# STeaMi-FP9-Bouton_de_controle.net
KiCad netlist of a schematic drawn in Altium Designer
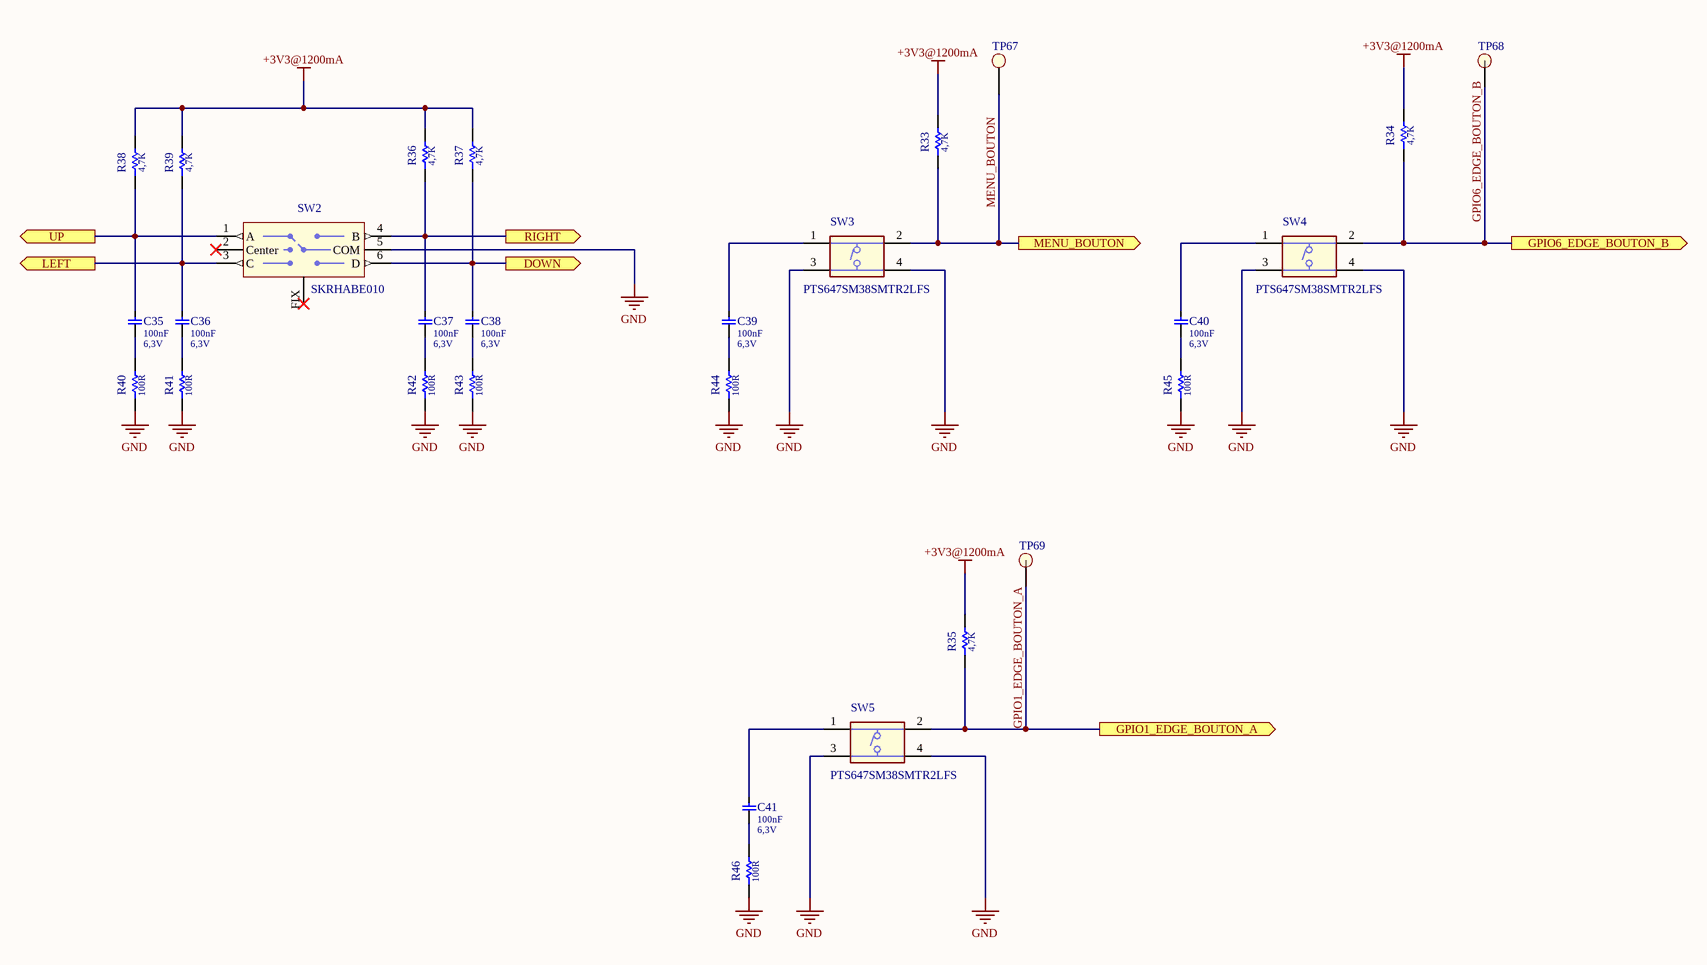
[diagram p0: STeaMi-FP9-Bouton_de_controle.SchDoc]

(export (version "E")
  (design (tool "Eeschema 10.0.6"))
  (components
    (comp (ref "C35")
      (value "~")
      (footprint "0402-CAP")
      (description "CAP CER 100nF 6,3V X5R 0402")
      (fields
        (field (name "MANUFACTURER") "Kyocera AVX")
        (field (name "MANUFACTURER PART NUMBER") "0402YD104KAT2A")
        (field (name "CAPACITANCE") "100nF")
        (field (name "VOLTAGE") "6,3V")
        (field (name "CREATED BY") "EAG")
        (field (name "CHECKED BY") "*")
      )
      (libsource (lib "ComponentDB") (part "CAP_SYMBOL"))
    )
    (comp (ref "C36")
      (value "~")
      (footprint "0402-CAP")
      (description "CAP CER 100nF 6,3V X5R 0402")
      (fields
        (field (name "MANUFACTURER") "Kyocera AVX")
        (field (name "MANUFACTURER PART NUMBER") "0402YD104KAT2A")
        (field (name "CAPACITANCE") "100nF")
        (field (name "VOLTAGE") "6,3V")
        (field (name "CREATED BY") "EAG")
        (field (name "CHECKED BY") "*")
      )
      (libsource (lib "ComponentDB") (part "CAP_SYMBOL"))
    )
    (comp (ref "C37")
      (value "~")
      (footprint "0402-CAP")
      (description "CAP CER 100nF 6,3V X5R 0402")
      (fields
        (field (name "MANUFACTURER") "Kyocera AVX")
        (field (name "MANUFACTURER PART NUMBER") "0402YD104KAT2A")
        (field (name "CAPACITANCE") "100nF")
        (field (name "VOLTAGE") "6,3V")
        (field (name "CREATED BY") "EAG")
        (field (name "CHECKED BY") "*")
      )
      (libsource (lib "ComponentDB") (part "CAP_SYMBOL"))
    )
    (comp (ref "C38")
      (value "~")
      (footprint "0402-CAP")
      (description "CAP CER 100nF 6,3V X5R 0402")
      (fields
        (field (name "MANUFACTURER") "Kyocera AVX")
        (field (name "MANUFACTURER PART NUMBER") "0402YD104KAT2A")
        (field (name "CAPACITANCE") "100nF")
        (field (name "VOLTAGE") "6,3V")
        (field (name "CREATED BY") "EAG")
        (field (name "CHECKED BY") "*")
      )
      (libsource (lib "ComponentDB") (part "CAP_SYMBOL"))
    )
    (comp (ref "C39")
      (value "~")
      (footprint "0402-CAP")
      (description "CAP CER 100nF 6,3V X5R 0402")
      (fields
        (field (name "MANUFACTURER") "Kyocera AVX")
        (field (name "MANUFACTURER PART NUMBER") "0402YD104KAT2A")
        (field (name "CAPACITANCE") "100nF")
        (field (name "VOLTAGE") "6,3V")
        (field (name "CREATED BY") "EAG")
        (field (name "CHECKED BY") "*")
      )
      (libsource (lib "ComponentDB") (part "CAP_SYMBOL"))
    )
    (comp (ref "C40")
      (value "~")
      (footprint "0402-CAP")
      (description "CAP CER 100nF 6,3V X5R 0402")
      (fields
        (field (name "MANUFACTURER") "Kyocera AVX")
        (field (name "MANUFACTURER PART NUMBER") "0402YD104KAT2A")
        (field (name "CAPACITANCE") "100nF")
        (field (name "VOLTAGE") "6,3V")
        (field (name "CREATED BY") "EAG")
        (field (name "CHECKED BY") "*")
      )
      (libsource (lib "ComponentDB") (part "CAP_SYMBOL"))
    )
    (comp (ref "C41")
      (value "~")
      (footprint "0402-CAP")
      (description "CAP CER 100nF 6,3V X5R 0402")
      (fields
        (field (name "MANUFACTURER") "Kyocera AVX")
        (field (name "MANUFACTURER PART NUMBER") "0402YD104KAT2A")
        (field (name "CAPACITANCE") "100nF")
        (field (name "VOLTAGE") "6,3V")
        (field (name "CREATED BY") "EAG")
        (field (name "CHECKED BY") "*")
      )
      (libsource (lib "ComponentDB") (part "CAP_SYMBOL"))
    )
    (comp (ref "R33")
      (value "~")
      (footprint "RESC1005X40N_0402")
      (description "RES CMS 4,7K5%-0,0625W-0402 ±100ppm/°C")
      (fields
        (field (name "MANUFACTURER") "Yageo")
        (field (name "MANUFACTURER PART NUMBER") "AC0402JR-074K7L")
        (field (name "RESISTANCE") "4,7K")
        (field (name "CREATED BY") "EAG")
      )
      (libsource (lib "ComponentDB") (part "RES_SYMBOL"))
    )
    (comp (ref "R34")
      (value "~")
      (footprint "RESC1005X40N_0402")
      (description "RES CMS 4,7K5%-0,0625W-0402 ±100ppm/°C")
      (fields
        (field (name "MANUFACTURER") "Yageo")
        (field (name "MANUFACTURER PART NUMBER") "AC0402JR-074K7L")
        (field (name "RESISTANCE") "4,7K")
        (field (name "CREATED BY") "EAG")
      )
      (libsource (lib "ComponentDB") (part "RES_SYMBOL"))
    )
    (comp (ref "R35")
      (value "~")
      (footprint "RESC1005X40N_0402")
      (description "RES CMS 4,7K5%-0,0625W-0402 ±100ppm/°C")
      (fields
        (field (name "MANUFACTURER") "Yageo")
        (field (name "MANUFACTURER PART NUMBER") "AC0402JR-074K7L")
        (field (name "RESISTANCE") "4,7K")
        (field (name "CREATED BY") "EAG")
      )
      (libsource (lib "ComponentDB") (part "RES_SYMBOL"))
    )
    (comp (ref "R36")
      (value "~")
      (footprint "RESC1005X40N_0402")
      (description "RES CMS 4,7K5%-0,0625W-0402 ±100ppm/°C")
      (fields
        (field (name "MANUFACTURER") "Yageo")
        (field (name "MANUFACTURER PART NUMBER") "AC0402JR-074K7L")
        (field (name "RESISTANCE") "4,7K")
        (field (name "CREATED BY") "EAG")
      )
      (libsource (lib "ComponentDB") (part "RES_SYMBOL"))
    )
    (comp (ref "R37")
      (value "~")
      (footprint "RESC1005X40N_0402")
      (description "RES CMS 4,7K5%-0,0625W-0402 ±100ppm/°C")
      (fields
        (field (name "MANUFACTURER") "Yageo")
        (field (name "MANUFACTURER PART NUMBER") "AC0402JR-074K7L")
        (field (name "RESISTANCE") "4,7K")
        (field (name "CREATED BY") "EAG")
      )
      (libsource (lib "ComponentDB") (part "RES_SYMBOL"))
    )
    (comp (ref "R38")
      (value "~")
      (footprint "RESC1005X40N_0402")
      (description "RES CMS 4,7K5%-0,0625W-0402 ±100ppm/°C")
      (fields
        (field (name "MANUFACTURER") "Yageo")
        (field (name "MANUFACTURER PART NUMBER") "AC0402JR-074K7L")
        (field (name "RESISTANCE") "4,7K")
        (field (name "CREATED BY") "EAG")
      )
      (libsource (lib "ComponentDB") (part "RES_SYMBOL"))
    )
    (comp (ref "R39")
      (value "~")
      (footprint "RESC1005X40N_0402")
      (description "RES CMS 4,7K5%-0,0625W-0402 ±100ppm/°C")
      (fields
        (field (name "MANUFACTURER") "Yageo")
        (field (name "MANUFACTURER PART NUMBER") "AC0402JR-074K7L")
        (field (name "RESISTANCE") "4,7K")
        (field (name "CREATED BY") "EAG")
      )
      (libsource (lib "ComponentDB") (part "RES_SYMBOL"))
    )
    (comp (ref "R40")
      (value "~")
      (footprint "RESC1005X40N_0402")
      (description "RES CMS 100R5%-0,0625W-0402 ±100ppm/°C")
      (fields
        (field (name "MANUFACTURER") "Yageo")
        (field (name "MANUFACTURER PART NUMBER") "RC0402JR-07100RL")
        (field (name "RESISTANCE") "100R")
        (field (name "CREATED BY") "EAG")
      )
      (libsource (lib "ComponentDB") (part "RES_SYMBOL"))
    )
    (comp (ref "R41")
      (value "~")
      (footprint "RESC1005X40N_0402")
      (description "RES CMS 100R5%-0,0625W-0402 ±100ppm/°C")
      (fields
        (field (name "MANUFACTURER") "Yageo")
        (field (name "MANUFACTURER PART NUMBER") "RC0402JR-07100RL")
        (field (name "RESISTANCE") "100R")
        (field (name "CREATED BY") "EAG")
      )
      (libsource (lib "ComponentDB") (part "RES_SYMBOL"))
    )
    (comp (ref "R42")
      (value "~")
      (footprint "RESC1005X40N_0402")
      (description "RES CMS 100R5%-0,0625W-0402 ±100ppm/°C")
      (fields
        (field (name "MANUFACTURER") "Yageo")
        (field (name "MANUFACTURER PART NUMBER") "RC0402JR-07100RL")
        (field (name "RESISTANCE") "100R")
        (field (name "CREATED BY") "EAG")
      )
      (libsource (lib "ComponentDB") (part "RES_SYMBOL"))
    )
    (comp (ref "R43")
      (value "~")
      (footprint "RESC1005X40N_0402")
      (description "RES CMS 100R5%-0,0625W-0402 ±100ppm/°C")
      (fields
        (field (name "MANUFACTURER") "Yageo")
        (field (name "MANUFACTURER PART NUMBER") "RC0402JR-07100RL")
        (field (name "RESISTANCE") "100R")
        (field (name "CREATED BY") "EAG")
      )
      (libsource (lib "ComponentDB") (part "RES_SYMBOL"))
    )
    (comp (ref "R44")
      (value "~")
      (footprint "RESC1005X40N_0402")
      (description "RES CMS 100R5%-0,0625W-0402 ±100ppm/°C")
      (fields
        (field (name "MANUFACTURER") "Yageo")
        (field (name "MANUFACTURER PART NUMBER") "RC0402JR-07100RL")
        (field (name "RESISTANCE") "100R")
        (field (name "CREATED BY") "EAG")
      )
      (libsource (lib "ComponentDB") (part "RES_SYMBOL"))
    )
    (comp (ref "R45")
      (value "~")
      (footprint "RESC1005X40N_0402")
      (description "RES CMS 100R5%-0,0625W-0402 ±100ppm/°C")
      (fields
        (field (name "MANUFACTURER") "Yageo")
        (field (name "MANUFACTURER PART NUMBER") "RC0402JR-07100RL")
        (field (name "RESISTANCE") "100R")
        (field (name "CREATED BY") "EAG")
      )
      (libsource (lib "ComponentDB") (part "RES_SYMBOL"))
    )
    (comp (ref "R46")
      (value "~")
      (footprint "RESC1005X40N_0402")
      (description "RES CMS 100R5%-0,0625W-0402 ±100ppm/°C")
      (fields
        (field (name "MANUFACTURER") "Yageo")
        (field (name "MANUFACTURER PART NUMBER") "RC0402JR-07100RL")
        (field (name "RESISTANCE") "100R")
        (field (name "CREATED BY") "EAG")
      )
      (libsource (lib "ComponentDB") (part "RES_SYMBOL"))
    )
    (comp (ref "SW2")
      (value "~")
      (footprint "SKRHABE010")
      (description "4-direction type with center-push function")
      (fields
        (field (name "MANUFACTURER") "ALPS")
        (field (name "MANUFACTURER PART NUMBER") "SKRHABE010")
        (field (name "PART NUMBER") "SKRHABE010")
        (field (name "CREATED BY") "EAG")
        (field (name "CHECKED BY") "*")
      )
      (libsource (lib "ComponentDB") (part "SKRHABE010"))
    )
    (comp (ref "SW3")
      (value "~")
      (footprint "PTS647SM38SMTR2LFS")
      (description "Interrupteurs de contact 50mA 12VDC, 1.8N 3.8mm H, G leads")
      (fields
        (field (name "MANUFACTURER") "C&K")
        (field (name "MANUFACTURER PART NUMBER") "PTS647SM38SMTR2LFS")
        (field (name "PART NUMBER") "PTS647SM38SMTR2LFS")
        (field (name "CREATED BY") "EAG")
        (field (name "CHECKED BY") "*")
      )
      (libsource (lib "ComponentDB") (part "PTS647SM38SMTR2LFS"))
    )
    (comp (ref "SW4")
      (value "~")
      (footprint "PTS647SM38SMTR2LFS")
      (description "Interrupteurs de contact 50mA 12VDC, 1.8N 3.8mm H, G leads")
      (fields
        (field (name "MANUFACTURER") "C&K")
        (field (name "MANUFACTURER PART NUMBER") "PTS647SM38SMTR2LFS")
        (field (name "PART NUMBER") "PTS647SM38SMTR2LFS")
        (field (name "CREATED BY") "EAG")
        (field (name "CHECKED BY") "*")
      )
      (libsource (lib "ComponentDB") (part "PTS647SM38SMTR2LFS"))
    )
    (comp (ref "SW5")
      (value "~")
      (footprint "PTS647SM38SMTR2LFS")
      (description "Interrupteurs de contact 50mA 12VDC, 1.8N 3.8mm H, G leads")
      (fields
        (field (name "MANUFACTURER") "C&K")
        (field (name "MANUFACTURER PART NUMBER") "PTS647SM38SMTR2LFS")
        (field (name "PART NUMBER") "PTS647SM38SMTR2LFS")
        (field (name "CREATED BY") "EAG")
        (field (name "CHECKED BY") "*")
      )
      (libsource (lib "ComponentDB") (part "PTS647SM38SMTR2LFS"))
    )
    (comp (ref "TP67")
      (value "PAD")
      (footprint "Testpoint 1mm")
      (description "TESTPOINTPAD")
      (fields (field (name "MANUFACTURER") "SmartEmbed"))
      (libsource (lib "") (part "TESTPOINT_1"))
    )
    (comp (ref "TP68")
      (value "PAD")
      (footprint "Testpoint 1mm")
      (description "TESTPOINTPAD")
      (fields (field (name "MANUFACTURER") "SmartEmbed"))
      (libsource (lib "ComponentDB") (part "TESTPOINT"))
    )
    (comp (ref "TP69")
      (value "PAD")
      (footprint "Testpoint 1mm")
      (description "TESTPOINTPAD")
      (fields (field (name "MANUFACTURER") "SmartEmbed"))
      (libsource (lib "ComponentDB") (part "TESTPOINT"))
    )
  )
  (nets
    (net (code "1") (name "+3V3@1200mA") (class "Default")
      (node (ref "R33") (pin "2") (pinfunction "2_2") (pintype "passive"))
      (node (ref "R34") (pin "2") (pinfunction "2_2") (pintype "passive"))
      (node (ref "R35") (pin "2") (pinfunction "2_2") (pintype "passive"))
      (node (ref "R36") (pin "2") (pinfunction "2_2") (pintype "passive"))
      (node (ref "R37") (pin "2") (pinfunction "2_2") (pintype "passive"))
      (node (ref "R38") (pin "2") (pinfunction "2_2") (pintype "passive"))
      (node (ref "R39") (pin "2") (pinfunction "2_2") (pintype "passive"))
    )
    (net (code "2") (name "/DOWN") (class "Default")
      (node (ref "C38") (pin "2") (pinfunction "2_2") (pintype "passive"))
      (node (ref "R37") (pin "1") (pinfunction "1_1") (pintype "passive"))
      (node (ref "SW2") (pin "6") (pinfunction "D_6") (pintype "output"))
    )
    (net (code "3") (name "/GPIO1_EDGE_BOUTON_A") (class "Default")
      (node (ref "R35") (pin "1") (pinfunction "1_1") (pintype "passive"))
      (node (ref "SW5") (pin "2") (pinfunction "2_2") (pintype "passive"))
      (node (ref "TP69") (pin "1") (pinfunction "1_1") (pintype "passive"))
    )
    (net (code "4") (name "/GPIO6_EDGE_BOUTON_B") (class "Default")
      (node (ref "R34") (pin "1") (pinfunction "1_1") (pintype "passive"))
      (node (ref "SW4") (pin "2") (pinfunction "2_2") (pintype "passive"))
      (node (ref "TP68") (pin "1") (pinfunction "1_1") (pintype "passive"))
    )
    (net (code "5") (name "/LEFT") (class "Default")
      (node (ref "C36") (pin "2") (pinfunction "2_2") (pintype "passive"))
      (node (ref "R39") (pin "1") (pinfunction "1_1") (pintype "passive"))
      (node (ref "SW2") (pin "3") (pinfunction "C_3") (pintype "output"))
    )
    (net (code "6") (name "/MENU_BOUTON") (class "Default")
      (node (ref "R33") (pin "1") (pinfunction "1_1") (pintype "passive"))
      (node (ref "SW3") (pin "2") (pinfunction "2_2") (pintype "passive"))
      (node (ref "TP67") (pin "1") (pinfunction "1_1") (pintype "passive"))
    )
    (net (code "7") (name "/RIGHT") (class "Default")
      (node (ref "C37") (pin "2") (pinfunction "2_2") (pintype "passive"))
      (node (ref "R36") (pin "1") (pinfunction "1_1") (pintype "passive"))
      (node (ref "SW2") (pin "4") (pinfunction "B_4") (pintype "output"))
    )
    (net (code "8") (name "/UP") (class "Default")
      (node (ref "C35") (pin "2") (pinfunction "2_2") (pintype "passive"))
      (node (ref "R38") (pin "1") (pinfunction "1_1") (pintype "passive"))
      (node (ref "SW2") (pin "1") (pinfunction "A_1") (pintype "output"))
    )
    (net (code "9") (name "GND") (class "Default")
      (node (ref "R40") (pin "1") (pinfunction "1_1") (pintype "passive"))
      (node (ref "R41") (pin "1") (pinfunction "1_1") (pintype "passive"))
      (node (ref "R42") (pin "1") (pinfunction "1_1") (pintype "passive"))
      (node (ref "R43") (pin "1") (pinfunction "1_1") (pintype "passive"))
      (node (ref "R44") (pin "1") (pinfunction "1_1") (pintype "passive"))
      (node (ref "R45") (pin "1") (pinfunction "1_1") (pintype "passive"))
      (node (ref "R46") (pin "1") (pinfunction "1_1") (pintype "passive"))
      (node (ref "SW2") (pin "5") (pinfunction "COM_5") (pintype "passive"))
      (node (ref "SW3") (pin "3") (pinfunction "3_3") (pintype "passive"))
      (node (ref "SW3") (pin "4") (pinfunction "4_4") (pintype "passive"))
      (node (ref "SW4") (pin "3") (pinfunction "3_3") (pintype "passive"))
      (node (ref "SW4") (pin "4") (pinfunction "4_4") (pintype "passive"))
      (node (ref "SW5") (pin "3") (pinfunction "3_3") (pintype "passive"))
      (node (ref "SW5") (pin "4") (pinfunction "4_4") (pintype "passive"))
    )
    (net (code "10") (name "Net-(C35-Pad1)") (class "Default")
      (node (ref "C35") (pin "1") (pinfunction "1_1") (pintype "passive"))
      (node (ref "R40") (pin "2") (pinfunction "2_2") (pintype "passive"))
    )
    (net (code "11") (name "Net-(C36-Pad1)") (class "Default")
      (node (ref "C36") (pin "1") (pinfunction "1_1") (pintype "passive"))
      (node (ref "R41") (pin "2") (pinfunction "2_2") (pintype "passive"))
    )
    (net (code "12") (name "Net-(C37-Pad1)") (class "Default")
      (node (ref "C37") (pin "1") (pinfunction "1_1") (pintype "passive"))
      (node (ref "R42") (pin "2") (pinfunction "2_2") (pintype "passive"))
    )
    (net (code "13") (name "Net-(C38-Pad1)") (class "Default")
      (node (ref "C38") (pin "1") (pinfunction "1_1") (pintype "passive"))
      (node (ref "R43") (pin "2") (pinfunction "2_2") (pintype "passive"))
    )
    (net (code "14") (name "Net-(C39-Pad1)") (class "Default")
      (node (ref "C39") (pin "1") (pinfunction "1_1") (pintype "passive"))
      (node (ref "R44") (pin "2") (pinfunction "2_2") (pintype "passive"))
    )
    (net (code "15") (name "Net-(C39-Pad2)") (class "Default")
      (node (ref "C39") (pin "2") (pinfunction "2_2") (pintype "passive"))
      (node (ref "SW3") (pin "1") (pinfunction "1_1") (pintype "passive"))
    )
    (net (code "16") (name "Net-(C40-Pad1)") (class "Default")
      (node (ref "C40") (pin "1") (pinfunction "1_1") (pintype "passive"))
      (node (ref "R45") (pin "2") (pinfunction "2_2") (pintype "passive"))
    )
    (net (code "17") (name "Net-(C40-Pad2)") (class "Default")
      (node (ref "C40") (pin "2") (pinfunction "2_2") (pintype "passive"))
      (node (ref "SW4") (pin "1") (pinfunction "1_1") (pintype "passive"))
    )
    (net (code "18") (name "Net-(C41-Pad1)") (class "Default")
      (node (ref "C41") (pin "1") (pinfunction "1_1") (pintype "passive"))
      (node (ref "R46") (pin "2") (pinfunction "2_2") (pintype "passive"))
    )
    (net (code "19") (name "Net-(C41-Pad2)") (class "Default")
      (node (ref "C41") (pin "2") (pinfunction "2_2") (pintype "passive"))
      (node (ref "SW5") (pin "1") (pinfunction "1_1") (pintype "passive"))
    )
    (net (code "20") (name "unconnected-(SW2-Center-Pad2)") (class "Default")
      (node (ref "SW2") (pin "2") (pinfunction "Center_2") (pintype "passive+no_connect"))
    )
    (net (code "21") (name "unconnected-(SW2-PadFIX)") (class "Default")
      (node (ref "SW2") (pin "FIX") (pinfunction "FIX_FIX") (pintype "passive+no_connect"))
    )
  )
)
